# cj732.net
KiCad netlist of a schematic drawn in EAGLE
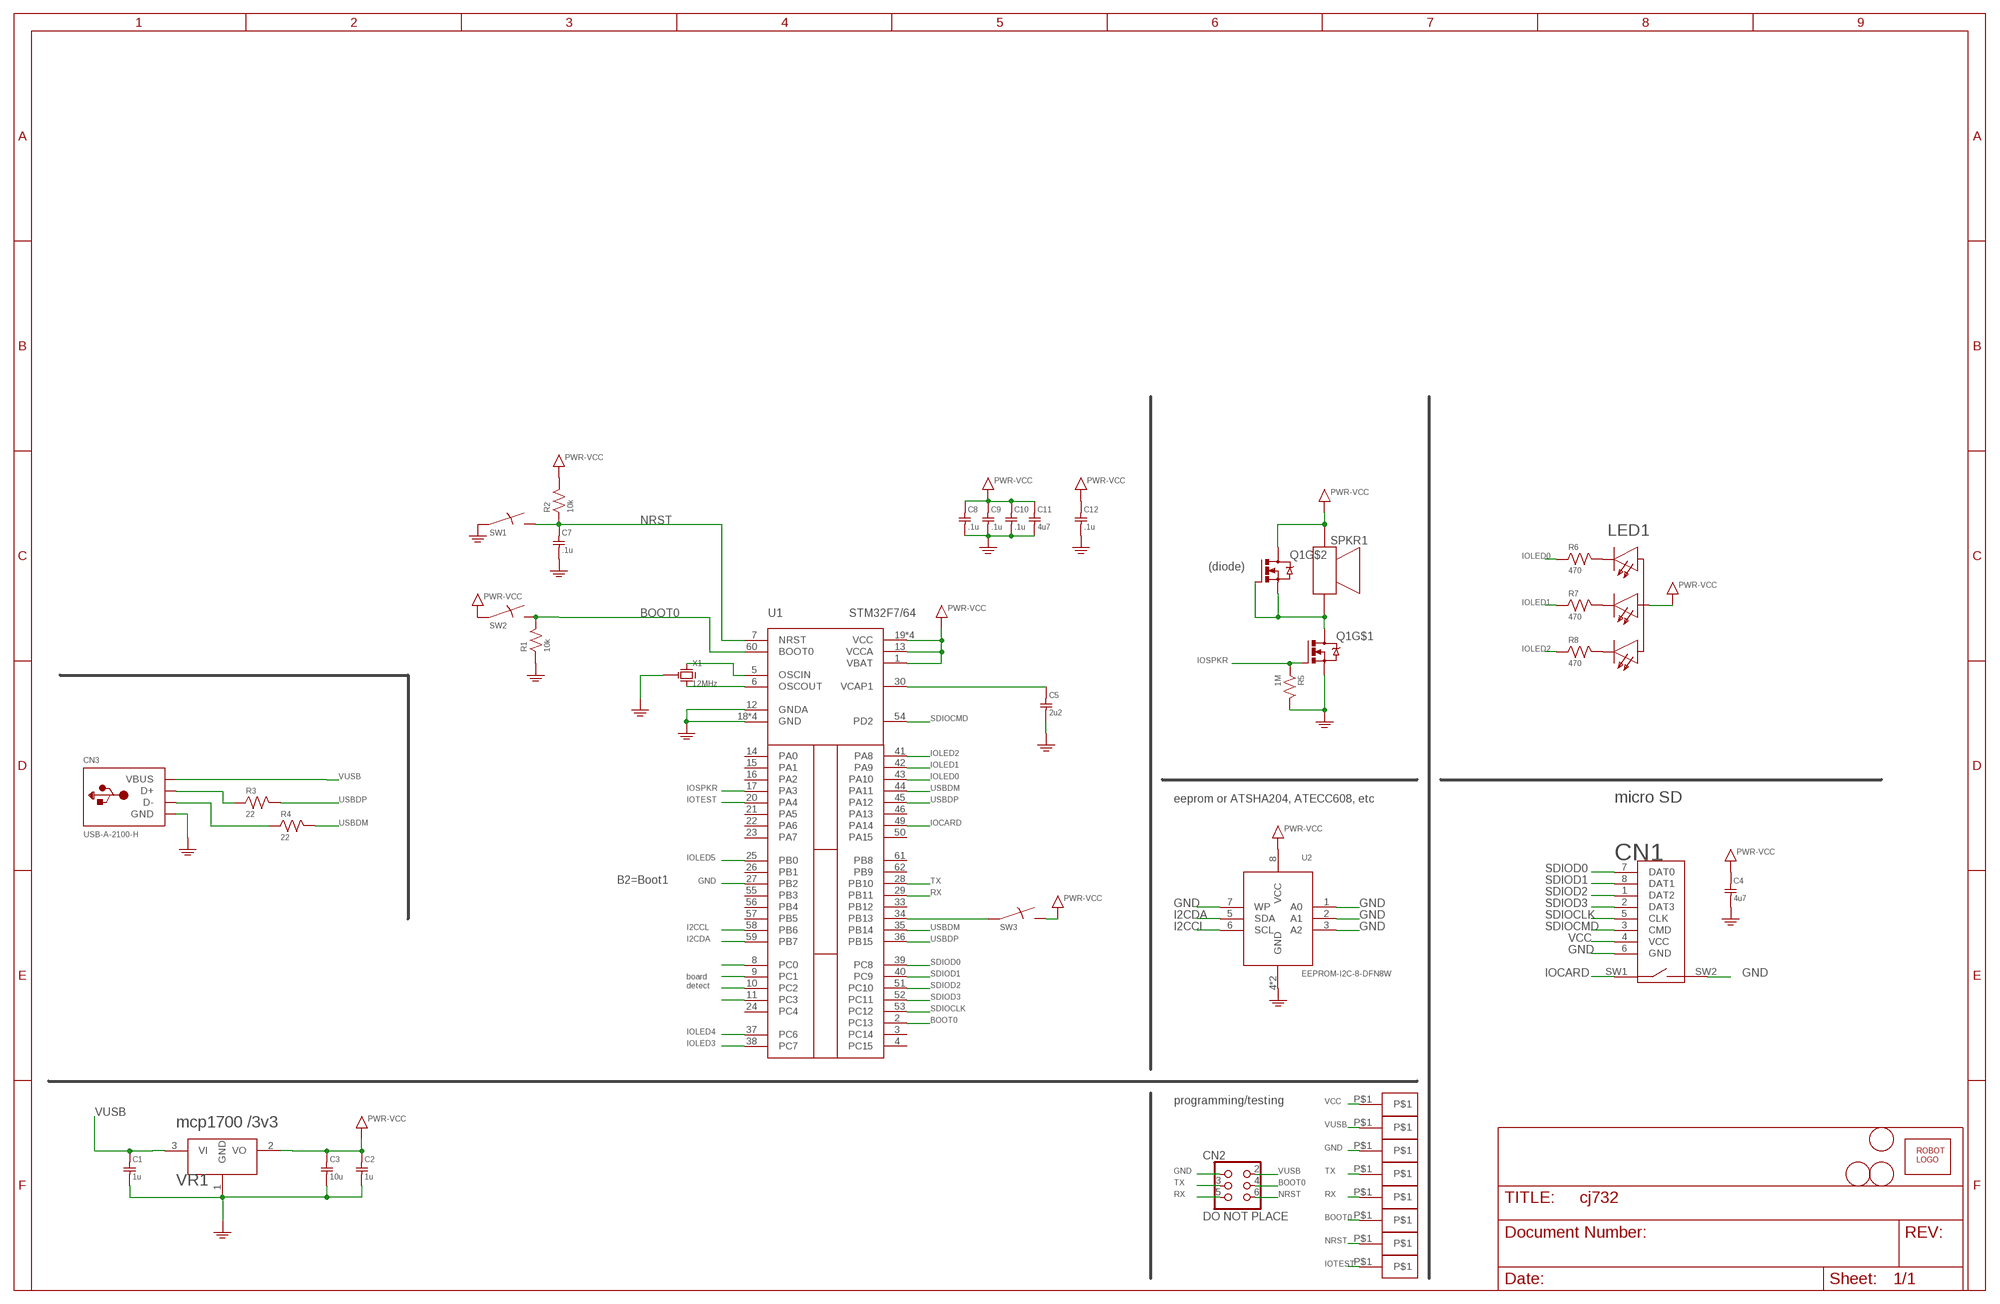
[diagram p0: schematic, sheet 1]

(export (version "E")
  (design (tool "Eeschema 10.0.6"))
  (components
    (comp (ref "C1")
      (value "1u")
      (footprint "eagle-import:SMD0603")
      (libsource (lib "eagle-import") (part "C0603"))
    )
    (comp (ref "C2")
      (value "1u")
      (footprint "eagle-import:SMD0603")
      (libsource (lib "eagle-import") (part "C0603"))
    )
    (comp (ref "C3")
      (value "10u")
      (footprint "eagle-import:SMD0603")
      (libsource (lib "eagle-import") (part "C0603"))
    )
    (comp (ref "C4")
      (value "4u7")
      (footprint "eagle-import:SMD0603")
      (libsource (lib "eagle-import") (part "C0603"))
    )
    (comp (ref "C5")
      (value "2u2")
      (footprint "eagle-import:SMD0603")
      (libsource (lib "eagle-import") (part "C0603"))
    )
    (comp (ref "C7")
      (value ".1u")
      (footprint "eagle-import:SMD0603")
      (libsource (lib "eagle-import") (part "C0603"))
    )
    (comp (ref "C8")
      (value ".1u")
      (footprint "eagle-import:SMD0603")
      (libsource (lib "eagle-import") (part "C0603"))
    )
    (comp (ref "C9")
      (value ".1u")
      (footprint "eagle-import:SMD0603")
      (libsource (lib "eagle-import") (part "C0603"))
    )
    (comp (ref "C10")
      (value ".1u")
      (footprint "eagle-import:SMD0603")
      (libsource (lib "eagle-import") (part "C0603"))
    )
    (comp (ref "C11")
      (value "4u7")
      (footprint "eagle-import:SMD0603")
      (libsource (lib "eagle-import") (part "C0603"))
    )
    (comp (ref "C12")
      (value ".1u")
      (footprint "eagle-import:SMD0603")
      (libsource (lib "eagle-import") (part "C0603"))
    )
    (comp (ref "CN1")
      (value "MICROSDPLAIN")
      (footprint "eagle-import:MICROSD_MOLEX_FRONT_PLAIN")
      (libsource (lib "eagle-import") (part "MICROSDPLAIN"))
    )
    (comp (ref "CN2")
      (value "DO NOT PLACE")
      (footprint "eagle-import:HEADER-3X2-PTH1.27")
      (libsource (lib "eagle-import") (part "HEADER-3X2-PTH1.27"))
    )
    (comp (ref "CN3")
      (value "USB-A-2100-H")
      (footprint "eagle-import:MOLEX_480372100-HOLE")
      (libsource (lib "eagle-import") (part "USB-A-2100-H"))
    )
    (comp (ref "CN4")
      (value "HEADER-1X1-SPOT")
      (footprint "eagle-import:SPOT")
      (libsource (lib "eagle-import") (part "HEADER-1X1-SPOT"))
    )
    (comp (ref "CN5")
      (value "HEADER-1X1-SPOT")
      (footprint "eagle-import:SPOT")
      (libsource (lib "eagle-import") (part "HEADER-1X1-SPOT"))
    )
    (comp (ref "CN6")
      (value "HEADER-1X1-SPOT")
      (footprint "eagle-import:SPOT")
      (libsource (lib "eagle-import") (part "HEADER-1X1-SPOT"))
    )
    (comp (ref "CN7")
      (value "HEADER-1X1-SPOT")
      (footprint "eagle-import:SPOT")
      (libsource (lib "eagle-import") (part "HEADER-1X1-SPOT"))
    )
    (comp (ref "CN8")
      (value "HEADER-1X1-SPOT")
      (footprint "eagle-import:SPOT")
      (libsource (lib "eagle-import") (part "HEADER-1X1-SPOT"))
    )
    (comp (ref "CN9")
      (value "HEADER-1X1-SPOT")
      (footprint "eagle-import:SPOT")
      (libsource (lib "eagle-import") (part "HEADER-1X1-SPOT"))
    )
    (comp (ref "CN10")
      (value "HEADER-1X1-SPOT")
      (footprint "eagle-import:SPOT")
      (libsource (lib "eagle-import") (part "HEADER-1X1-SPOT"))
    )
    (comp (ref "CN11")
      (value "HEADER-1X1-SPOT")
      (footprint "eagle-import:SPOT")
      (libsource (lib "eagle-import") (part "HEADER-1X1-SPOT"))
    )
    (comp (ref "LED1")
      (value "LED-RGB-CA-PLCC4")
      (footprint "eagle-import:PLCC4-3228")
      (libsource (lib "eagle-import") (part "LED-RGB-CA-PLCC4"))
    )
    (comp (ref "Q1")
      (value "MOSFET-2N")
      (footprint "eagle-import:SC-70-6")
      (libsource (lib "eagle-import") (part "MOSFET-2N"))
    )
    (comp (ref "R1")
      (value "10k")
      (footprint "eagle-import:SMD0603")
      (libsource (lib "eagle-import") (part "R0603"))
    )
    (comp (ref "R2")
      (value "10k")
      (footprint "eagle-import:SMD0603")
      (libsource (lib "eagle-import") (part "R0603"))
    )
    (comp (ref "R3")
      (value "22")
      (footprint "eagle-import:SMD0603")
      (libsource (lib "eagle-import") (part "R0603"))
    )
    (comp (ref "R4")
      (value "22")
      (footprint "eagle-import:SMD0603")
      (libsource (lib "eagle-import") (part "R0603"))
    )
    (comp (ref "R5")
      (value "1M")
      (footprint "eagle-import:SMD0603")
      (libsource (lib "eagle-import") (part "R0603"))
    )
    (comp (ref "R6")
      (value "470")
      (footprint "eagle-import:SMD0603")
      (libsource (lib "eagle-import") (part "R0603"))
    )
    (comp (ref "R7")
      (value "470")
      (footprint "eagle-import:SMD0603")
      (libsource (lib "eagle-import") (part "R0603"))
    )
    (comp (ref "R8")
      (value "470")
      (footprint "eagle-import:SMD0603")
      (libsource (lib "eagle-import") (part "R0603"))
    )
    (comp (ref "SPKR1")
      (value "SPKR-PUI-0440")
      (footprint "eagle-import:PUI-0440")
      (libsource (lib "eagle-import") (part "SPKR-PUI-0440"))
    )
    (comp (ref "SW1")
      (value "SWITCH-PTS810")
      (footprint "eagle-import:PTS810")
      (libsource (lib "eagle-import") (part "SWITCH-PTS810"))
    )
    (comp (ref "SW2")
      (value "SWITCH-PTS810")
      (footprint "eagle-import:PTS810")
      (libsource (lib "eagle-import") (part "SWITCH-PTS810"))
    )
    (comp (ref "SW3")
      (value "SWITCH-PTS810")
      (footprint "eagle-import:PTS810")
      (libsource (lib "eagle-import") (part "SWITCH-PTS810"))
    )
    (comp (ref "U$1")
      (value "ROBOTMAN-LOGO")
      (footprint "eagle-import:ROBOTMAN-LOGO")
      (libsource (lib "eagle-import") (part "ROBOTMAN-LOGO"))
    )
    (comp (ref "U$2")
      (value "FIDUCIAL")
      (footprint "eagle-import:FIDUCIAL_1MM")
      (libsource (lib "eagle-import") (part "FIDUCIAL"))
    )
    (comp (ref "U$3")
      (value "FIDUCIAL")
      (footprint "eagle-import:FIDUCIAL_1MM")
      (libsource (lib "eagle-import") (part "FIDUCIAL"))
    )
    (comp (ref "U$4")
      (value "FIDUCIAL")
      (footprint "eagle-import:FIDUCIAL_1MM")
      (libsource (lib "eagle-import") (part "FIDUCIAL"))
    )
    (comp (ref "U1")
      (value "STM32F7/64")
      (footprint "eagle-import:TQFP64")
      (libsource (lib "eagle-import") (part "STM32F7/64"))
    )
    (comp (ref "U2")
      (value "EEPROM-I2C-8-DFN8W")
      (footprint "eagle-import:TDFN8EPW")
      (libsource (lib "eagle-import") (part "EEPROM-I2C-8-DFN8W"))
    )
    (comp (ref "VR1")
      (value "mcp1700 /3v3")
      (footprint "eagle-import:SOT-23-3@1")
      (libsource (lib "eagle-import") (part "REGULATOR-SOT23-3"))
    )
    (comp (ref "X1")
      (value "12MHz")
      (footprint "eagle-import:RESONATOR-CSTCE")
      (libsource (lib "eagle-import") (part "RESONATORCTCE"))
    )
  )
  (nets
    (net (code "1") (name "/BOOT0") (class "Default")
      (node (ref "CN2") (pin "4") (pinfunction "P$4_4") (pintype "passive"))
      (node (ref "CN8") (pin "P$1") (pinfunction "P$1_P$1") (pintype "bidirectional"))
      (node (ref "R1") (pin "2") (pinfunction "P$2_2") (pintype "passive"))
      (node (ref "SW2") (pin "P$2") (pinfunction "P$2_P$2") (pintype "passive"))
      (node (ref "SW2") (pin "P$2B") (pinfunction "P$2_P$2B") (pintype "passive"))
      (node (ref "U1") (pin "2") (pinfunction "PC13_2") (pintype "bidirectional"))
      (node (ref "U1") (pin "60") (pinfunction "BOOT0_60") (pintype "bidirectional"))
    )
    (net (code "2") (name "/I2CCL") (class "Default")
      (node (ref "U1") (pin "58") (pinfunction "PB6_58") (pintype "bidirectional"))
      (node (ref "U2") (pin "6") (pinfunction "SCL_6") (pintype "bidirectional"))
    )
    (net (code "3") (name "/I2CDA") (class "Default")
      (node (ref "U1") (pin "59") (pinfunction "PB7_59") (pintype "bidirectional"))
      (node (ref "U2") (pin "5") (pinfunction "SDA_5") (pintype "bidirectional"))
    )
    (net (code "4") (name "/IOCARD") (class "Default")
      (node (ref "CN1") (pin "SW1") (pinfunction "SW1_SW1") (pintype "bidirectional"))
      (node (ref "U1") (pin "49") (pinfunction "PA14_49") (pintype "bidirectional"))
    )
    (net (code "5") (name "/IOLED0") (class "Default")
      (node (ref "R6") (pin "1") (pinfunction "P$1_1") (pintype "passive"))
      (node (ref "U1") (pin "43") (pinfunction "PA10_43") (pintype "bidirectional"))
    )
    (net (code "6") (name "/IOLED1") (class "Default")
      (node (ref "R7") (pin "1") (pinfunction "P$1_1") (pintype "passive"))
      (node (ref "U1") (pin "42") (pinfunction "PA9_42") (pintype "bidirectional"))
    )
    (net (code "7") (name "/IOLED2") (class "Default")
      (node (ref "R8") (pin "1") (pinfunction "P$1_1") (pintype "passive"))
      (node (ref "U1") (pin "41") (pinfunction "PA8_41") (pintype "bidirectional"))
    )
    (net (code "8") (name "/IOLED3") (class "Default")
      (node (ref "U1") (pin "38") (pinfunction "PC7_38") (pintype "bidirectional"))
    )
    (net (code "9") (name "/IOLED4") (class "Default")
      (node (ref "U1") (pin "37") (pinfunction "PC6_37") (pintype "bidirectional"))
    )
    (net (code "10") (name "/IOLED5") (class "Default")
      (node (ref "U1") (pin "25") (pinfunction "PB0_25") (pintype "bidirectional"))
    )
    (net (code "11") (name "/IOSPKR") (class "Default")
      (node (ref "Q1") (pin "2") (pinfunction "G_2") (pintype "passive"))
      (node (ref "R5") (pin "1") (pinfunction "P$1_1") (pintype "passive"))
      (node (ref "U1") (pin "17") (pinfunction "PA3_17") (pintype "bidirectional"))
    )
    (net (code "12") (name "/IOTEST") (class "Default")
      (node (ref "CN11") (pin "P$1") (pinfunction "P$1_P$1") (pintype "bidirectional"))
      (node (ref "U1") (pin "20") (pinfunction "PA4_20") (pintype "bidirectional"))
    )
    (net (code "13") (name "/NRST") (class "Default")
      (node (ref "C7") (pin "1") (pinfunction "P$1_1") (pintype "passive"))
      (node (ref "CN2") (pin "6") (pinfunction "P$6_6") (pintype "passive"))
      (node (ref "CN9") (pin "P$1") (pinfunction "P$1_P$1") (pintype "bidirectional"))
      (node (ref "R2") (pin "1") (pinfunction "P$1_1") (pintype "passive"))
      (node (ref "SW1") (pin "P$2") (pinfunction "P$2_P$2") (pintype "passive"))
      (node (ref "SW1") (pin "P$2B") (pinfunction "P$2_P$2B") (pintype "passive"))
      (node (ref "U1") (pin "7") (pinfunction "NRST_7") (pintype "bidirectional"))
    )
    (net (code "14") (name "/RX") (class "Default")
      (node (ref "CN2") (pin "5") (pinfunction "P$5_5") (pintype "passive"))
      (node (ref "CN7") (pin "P$1") (pinfunction "P$1_P$1") (pintype "bidirectional"))
      (node (ref "U1") (pin "29") (pinfunction "PB11_29") (pintype "bidirectional"))
    )
    (net (code "15") (name "/SDIOCLK") (class "Default")
      (node (ref "CN1") (pin "5") (pinfunction "CLK_5") (pintype "bidirectional"))
      (node (ref "U1") (pin "53") (pinfunction "PC12_53") (pintype "bidirectional"))
    )
    (net (code "16") (name "/SDIOCMD") (class "Default")
      (node (ref "CN1") (pin "3") (pinfunction "CMD_3") (pintype "bidirectional"))
      (node (ref "U1") (pin "54") (pinfunction "PD2_54") (pintype "bidirectional"))
    )
    (net (code "17") (name "/SDIOD0") (class "Default")
      (node (ref "CN1") (pin "7") (pinfunction "DAT0_7") (pintype "bidirectional"))
      (node (ref "U1") (pin "39") (pinfunction "PC8_39") (pintype "bidirectional"))
    )
    (net (code "18") (name "/SDIOD1") (class "Default")
      (node (ref "CN1") (pin "8") (pinfunction "DAT1_8") (pintype "bidirectional"))
      (node (ref "U1") (pin "40") (pinfunction "PC9_40") (pintype "bidirectional"))
    )
    (net (code "19") (name "/SDIOD2") (class "Default")
      (node (ref "CN1") (pin "1") (pinfunction "DAT2_1") (pintype "bidirectional"))
      (node (ref "U1") (pin "51") (pinfunction "PC10_51") (pintype "bidirectional"))
    )
    (net (code "20") (name "/SDIOD3") (class "Default")
      (node (ref "CN1") (pin "2") (pinfunction "DAT3_2") (pintype "bidirectional"))
      (node (ref "U1") (pin "52") (pinfunction "PC11_52") (pintype "bidirectional"))
    )
    (net (code "21") (name "/TX") (class "Default")
      (node (ref "CN2") (pin "3") (pinfunction "P$3_3") (pintype "passive"))
      (node (ref "CN6") (pin "P$1") (pinfunction "P$1_P$1") (pintype "bidirectional"))
      (node (ref "U1") (pin "28") (pinfunction "PB10_28") (pintype "bidirectional"))
    )
    (net (code "22") (name "/USBDM") (class "Default")
      (node (ref "R4") (pin "2") (pinfunction "P$2_2") (pintype "passive"))
      (node (ref "U1") (pin "35") (pinfunction "PB14_35") (pintype "bidirectional"))
      (node (ref "U1") (pin "44") (pinfunction "PA11_44") (pintype "bidirectional"))
    )
    (net (code "23") (name "/USBDP") (class "Default")
      (node (ref "R3") (pin "2") (pinfunction "P$2_2") (pintype "passive"))
      (node (ref "U1") (pin "36") (pinfunction "PB15_36") (pintype "bidirectional"))
      (node (ref "U1") (pin "45") (pinfunction "PA12_45") (pintype "bidirectional"))
    )
    (net (code "24") (name "/VUSB") (class "Default")
      (node (ref "C1") (pin "1") (pinfunction "P$1_1") (pintype "passive"))
      (node (ref "CN2") (pin "2") (pinfunction "P$2_2") (pintype "passive"))
      (node (ref "CN3") (pin "1") (pinfunction "VBUS_1") (pintype "power_in"))
      (node (ref "CN4") (pin "P$1") (pinfunction "P$1_P$1") (pintype "bidirectional"))
      (node (ref "VR1") (pin "3") (pinfunction "VI_3") (pintype "bidirectional"))
    )
    (net (code "25") (name "Net-(C5-P$1)") (class "Default")
      (node (ref "C5") (pin "1") (pinfunction "P$1_1") (pintype "passive"))
      (node (ref "U1") (pin "30") (pinfunction "VCAP1_30") (pintype "bidirectional"))
    )
    (net (code "26") (name "Net-(CN3-D+)") (class "Default")
      (node (ref "CN3") (pin "3") (pinfunction "D+_3") (pintype "bidirectional"))
      (node (ref "R3") (pin "1") (pinfunction "P$1_1") (pintype "passive"))
    )
    (net (code "27") (name "Net-(CN3-D-)") (class "Default")
      (node (ref "CN3") (pin "2") (pinfunction "D-_2") (pintype "bidirectional"))
      (node (ref "R4") (pin "1") (pinfunction "P$1_1") (pintype "passive"))
    )
    (net (code "28") (name "Net-(LED1-CB)") (class "Default")
      (node (ref "LED1") (pin "P$4") (pinfunction "CB_P$4") (pintype "passive"))
      (node (ref "R7") (pin "2") (pinfunction "P$2_2") (pintype "passive"))
    )
    (net (code "29") (name "Net-(LED1-CG)") (class "Default")
      (node (ref "LED1") (pin "P$3") (pinfunction "CG_P$3") (pintype "passive"))
      (node (ref "R6") (pin "2") (pinfunction "P$2_2") (pintype "passive"))
    )
    (net (code "30") (name "Net-(LED1-CR)") (class "Default")
      (node (ref "LED1") (pin "P$2") (pinfunction "CR_P$2") (pintype "passive"))
      (node (ref "R8") (pin "2") (pinfunction "P$2_2") (pintype "passive"))
    )
    (net (code "31") (name "Net-(Q1A-D)") (class "Default")
      (node (ref "Q1") (pin "4") (pinfunction "S_4") (pintype "passive"))
      (node (ref "Q1") (pin "5") (pinfunction "G_5") (pintype "passive"))
      (node (ref "Q1") (pin "6") (pinfunction "D_6") (pintype "passive"))
      (node (ref "SPKR1") (pin "P$2") (pinfunction "P2_P$2") (pintype "input"))
    )
    (net (code "32") (name "Net-(U1-OSCIN)") (class "Default")
      (node (ref "U1") (pin "5") (pinfunction "OSCIN_5") (pintype "bidirectional"))
      (node (ref "X1") (pin "1") (pinfunction "X1_1") (pintype "passive"))
    )
    (net (code "33") (name "Net-(U1-OSCOUT)") (class "Default")
      (node (ref "U1") (pin "6") (pinfunction "OSCOUT_6") (pintype "bidirectional"))
      (node (ref "X1") (pin "3") (pinfunction "X2_3") (pintype "passive"))
    )
    (net (code "34") (name "Net-(U1-PB13)") (class "Default")
      (node (ref "SW3") (pin "P$1") (pinfunction "P$1_P$1") (pintype "passive"))
      (node (ref "SW3") (pin "P$1B") (pinfunction "P$1_P$1B") (pintype "passive"))
      (node (ref "U1") (pin "34") (pinfunction "PB13_34") (pintype "bidirectional"))
    )
    (net (code "35") (name "PWR-GND") (class "Default")
      (node (ref "C1") (pin "2") (pinfunction "P$2_2") (pintype "passive"))
      (node (ref "C10") (pin "2") (pinfunction "P$2_2") (pintype "passive"))
      (node (ref "C11") (pin "2") (pinfunction "P$2_2") (pintype "passive"))
      (node (ref "C12") (pin "2") (pinfunction "P$2_2") (pintype "passive"))
      (node (ref "C2") (pin "2") (pinfunction "P$2_2") (pintype "passive"))
      (node (ref "C3") (pin "2") (pinfunction "P$2_2") (pintype "passive"))
      (node (ref "C4") (pin "2") (pinfunction "P$2_2") (pintype "passive"))
      (node (ref "C5") (pin "2") (pinfunction "P$2_2") (pintype "passive"))
      (node (ref "C7") (pin "2") (pinfunction "P$2_2") (pintype "passive"))
      (node (ref "C8") (pin "2") (pinfunction "P$2_2") (pintype "passive"))
      (node (ref "C9") (pin "2") (pinfunction "P$2_2") (pintype "passive"))
      (node (ref "CN1") (pin "6") (pinfunction "GND_6") (pintype "bidirectional"))
      (node (ref "CN1") (pin "SW2") (pinfunction "SW2_SW2") (pintype "bidirectional"))
      (node (ref "CN2") (pin "1") (pinfunction "P$1_1") (pintype "passive"))
      (node (ref "CN3") (pin "4") (pinfunction "GND_4") (pintype "power_in"))
      (node (ref "CN3") (pin "P$1") (pinfunction "GND_P$1") (pintype "power_in"))
      (node (ref "CN3") (pin "P$2") (pinfunction "GND_P$2") (pintype "power_in"))
      (node (ref "CN5") (pin "P$1") (pinfunction "P$1_P$1") (pintype "bidirectional"))
      (node (ref "Q1") (pin "1") (pinfunction "S_1") (pintype "passive"))
      (node (ref "R1") (pin "1") (pinfunction "P$1_1") (pintype "passive"))
      (node (ref "R5") (pin "2") (pinfunction "P$2_2") (pintype "passive"))
      (node (ref "SW1") (pin "P$1") (pinfunction "P$1_P$1") (pintype "passive"))
      (node (ref "SW1") (pin "P$1B") (pinfunction "P$1_P$1B") (pintype "passive"))
      (node (ref "U1") (pin "12") (pinfunction "GNDA_12") (pintype "bidirectional"))
      (node (ref "U1") (pin "18") (pinfunction "GND_18") (pintype "bidirectional"))
      (node (ref "U1") (pin "27") (pinfunction "PB2_27") (pintype "bidirectional"))
      (node (ref "U1") (pin "31") (pinfunction "GND_31") (pintype "bidirectional"))
      (node (ref "U1") (pin "47") (pinfunction "GND_47") (pintype "bidirectional"))
      (node (ref "U1") (pin "63") (pinfunction "GND_63") (pintype "bidirectional"))
      (node (ref "U2") (pin "1") (pinfunction "A0_1") (pintype "bidirectional"))
      (node (ref "U2") (pin "2") (pinfunction "A1_2") (pintype "bidirectional"))
      (node (ref "U2") (pin "3") (pinfunction "A2_3") (pintype "bidirectional"))
      (node (ref "U2") (pin "4") (pinfunction "GND_4") (pintype "bidirectional"))
      (node (ref "U2") (pin "7") (pinfunction "WP_7") (pintype "bidirectional"))
      (node (ref "U2") (pin "PAD") (pinfunction "GND_PAD") (pintype "bidirectional"))
      (node (ref "VR1") (pin "1") (pinfunction "GND_1") (pintype "bidirectional"))
      (node (ref "X1") (pin "2") (pinfunction "G_2") (pintype "input"))
    )
    (net (code "36") (name "PWR-VCC") (class "Default")
      (node (ref "C10") (pin "1") (pinfunction "P$1_1") (pintype "passive"))
      (node (ref "C11") (pin "1") (pinfunction "P$1_1") (pintype "passive"))
      (node (ref "C12") (pin "1") (pinfunction "P$1_1") (pintype "passive"))
      (node (ref "C2") (pin "1") (pinfunction "P$1_1") (pintype "passive"))
      (node (ref "C3") (pin "1") (pinfunction "P$1_1") (pintype "passive"))
      (node (ref "C4") (pin "1") (pinfunction "P$1_1") (pintype "passive"))
      (node (ref "C8") (pin "1") (pinfunction "P$1_1") (pintype "passive"))
      (node (ref "C9") (pin "1") (pinfunction "P$1_1") (pintype "passive"))
      (node (ref "CN1") (pin "4") (pinfunction "VCC_4") (pintype "bidirectional"))
      (node (ref "CN10") (pin "P$1") (pinfunction "P$1_P$1") (pintype "bidirectional"))
      (node (ref "LED1") (pin "P$1") (pinfunction "A_P$1") (pintype "passive"))
      (node (ref "Q1") (pin "3") (pinfunction "D_3") (pintype "passive"))
      (node (ref "R2") (pin "2") (pinfunction "P$2_2") (pintype "passive"))
      (node (ref "SPKR1") (pin "P$1") (pinfunction "P1_P$1") (pintype "input"))
      (node (ref "SW2") (pin "P$1") (pinfunction "P$1_P$1") (pintype "passive"))
      (node (ref "SW2") (pin "P$1B") (pinfunction "P$1_P$1B") (pintype "passive"))
      (node (ref "SW3") (pin "P$2") (pinfunction "P$2_P$2") (pintype "passive"))
      (node (ref "SW3") (pin "P$2B") (pinfunction "P$2_P$2B") (pintype "passive"))
      (node (ref "U1") (pin "1") (pinfunction "VBAT_1") (pintype "bidirectional"))
      (node (ref "U1") (pin "13") (pinfunction "VCCA_13") (pintype "bidirectional"))
      (node (ref "U1") (pin "19") (pinfunction "VCC_19") (pintype "bidirectional"))
      (node (ref "U1") (pin "32") (pinfunction "VCC_32") (pintype "bidirectional"))
      (node (ref "U1") (pin "48") (pinfunction "VCC_48") (pintype "bidirectional"))
      (node (ref "U1") (pin "64") (pinfunction "VCC_64") (pintype "bidirectional"))
      (node (ref "U2") (pin "8") (pinfunction "VCC_8") (pintype "bidirectional"))
      (node (ref "VR1") (pin "2") (pinfunction "VO_2") (pintype "bidirectional"))
    )
    (net (code "37") (name "unconnected-(U1-PA0-Pad14)") (class "Default")
      (node (ref "U1") (pin "14") (pinfunction "PA0_14") (pintype "bidirectional"))
    )
    (net (code "38") (name "unconnected-(U1-PA1-Pad15)") (class "Default")
      (node (ref "U1") (pin "15") (pinfunction "PA1_15") (pintype "bidirectional"))
    )
    (net (code "39") (name "unconnected-(U1-PA2-Pad16)") (class "Default")
      (node (ref "U1") (pin "16") (pinfunction "PA2_16") (pintype "bidirectional"))
    )
    (net (code "40") (name "unconnected-(U1-PA5-Pad21)") (class "Default")
      (node (ref "U1") (pin "21") (pinfunction "PA5_21") (pintype "bidirectional"))
    )
    (net (code "41") (name "unconnected-(U1-PA6-Pad22)") (class "Default")
      (node (ref "U1") (pin "22") (pinfunction "PA6_22") (pintype "bidirectional"))
    )
    (net (code "42") (name "unconnected-(U1-PA7-Pad23)") (class "Default")
      (node (ref "U1") (pin "23") (pinfunction "PA7_23") (pintype "bidirectional"))
    )
    (net (code "43") (name "unconnected-(U1-PA13-Pad46)") (class "Default")
      (node (ref "U1") (pin "46") (pinfunction "PA13_46") (pintype "bidirectional"))
    )
    (net (code "44") (name "unconnected-(U1-PA15-Pad50)") (class "Default")
      (node (ref "U1") (pin "50") (pinfunction "PA15_50") (pintype "bidirectional"))
    )
    (net (code "45") (name "unconnected-(U1-PB1-Pad26)") (class "Default")
      (node (ref "U1") (pin "26") (pinfunction "PB1_26") (pintype "bidirectional"))
    )
    (net (code "46") (name "unconnected-(U1-PB3-Pad55)") (class "Default")
      (node (ref "U1") (pin "55") (pinfunction "PB3_55") (pintype "bidirectional"))
    )
    (net (code "47") (name "unconnected-(U1-PB4-Pad56)") (class "Default")
      (node (ref "U1") (pin "56") (pinfunction "PB4_56") (pintype "bidirectional"))
    )
    (net (code "48") (name "unconnected-(U1-PB5-Pad57)") (class "Default")
      (node (ref "U1") (pin "57") (pinfunction "PB5_57") (pintype "bidirectional"))
    )
    (net (code "49") (name "unconnected-(U1-PB8-Pad61)") (class "Default")
      (node (ref "U1") (pin "61") (pinfunction "PB8_61") (pintype "bidirectional"))
    )
    (net (code "50") (name "unconnected-(U1-PB9-Pad62)") (class "Default")
      (node (ref "U1") (pin "62") (pinfunction "PB9_62") (pintype "bidirectional"))
    )
    (net (code "51") (name "unconnected-(U1-PB12-Pad33)") (class "Default")
      (node (ref "U1") (pin "33") (pinfunction "PB12_33") (pintype "bidirectional"))
    )
    (net (code "52") (name "unconnected-(U1-PC0-Pad8)") (class "Default")
      (node (ref "U1") (pin "8") (pinfunction "PC0_8") (pintype "bidirectional"))
    )
    (net (code "53") (name "unconnected-(U1-PC1-Pad9)") (class "Default")
      (node (ref "U1") (pin "9") (pinfunction "PC1_9") (pintype "bidirectional"))
    )
    (net (code "54") (name "unconnected-(U1-PC2-Pad10)") (class "Default")
      (node (ref "U1") (pin "10") (pinfunction "PC2_10") (pintype "bidirectional"))
    )
    (net (code "55") (name "unconnected-(U1-PC3-Pad11)") (class "Default")
      (node (ref "U1") (pin "11") (pinfunction "PC3_11") (pintype "bidirectional"))
    )
    (net (code "56") (name "unconnected-(U1-PC4-Pad24)") (class "Default")
      (node (ref "U1") (pin "24") (pinfunction "PC4_24") (pintype "bidirectional"))
    )
    (net (code "57") (name "unconnected-(U1-PC14-Pad3)") (class "Default")
      (node (ref "U1") (pin "3") (pinfunction "PC14_3") (pintype "bidirectional"))
    )
    (net (code "58") (name "unconnected-(U1-PC15-Pad4)") (class "Default")
      (node (ref "U1") (pin "4") (pinfunction "PC15_4") (pintype "bidirectional"))
    )
  )
)
